# Maple6r.net
KiCad netlist of a schematic drawn in EAGLE
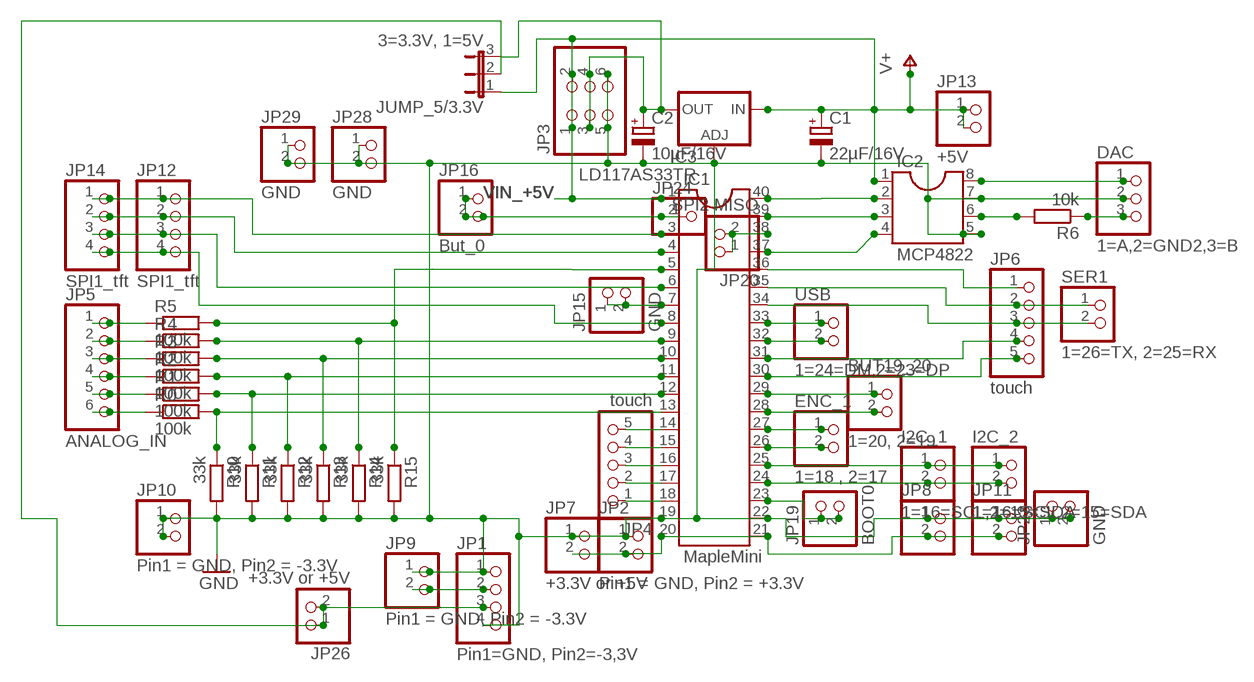
[diagram p0: schematic, sheet 1]

(export (version "E")
  (design (tool "Eeschema 10.0.6"))
  (components
    (comp (ref "BUT19_20")
      (value "1=20, 2=19")
      (footprint "eagle-import:1X02")
      (libsource (lib "eagle-import") (part "PINHD-1X2"))
    )
    (comp (ref "C1")
      (value "22µF/16V")
      (footprint "eagle-import:E5-8,5")
      (libsource (lib "eagle-import") (part "CPOL-EUE5-8.5"))
    )
    (comp (ref "C2")
      (value "10µF/16V")
      (footprint "eagle-import:E5-8,5")
      (libsource (lib "eagle-import") (part "CPOL-EUE5-8.5"))
    )
    (comp (ref "DAC")
      (value "1=A,2=GND2,3=B")
      (footprint "eagle-import:1X03")
      (libsource (lib "eagle-import") (part "PINHD-1X3"))
    )
    (comp (ref "ENC_1")
      (value "1=18 , 2=17")
      (footprint "eagle-import:1X02")
      (libsource (lib "eagle-import") (part "PINHD-1X2"))
    )
    (comp (ref "I2C_1")
      (value "1=16=SCL,2=15=SDA")
      (footprint "eagle-import:1X02")
      (libsource (lib "eagle-import") (part "PINHD-1X2"))
    )
    (comp (ref "I2C_2")
      (value "1=16=SCL,2=15=SDA")
      (footprint "eagle-import:1X02")
      (libsource (lib "eagle-import") (part "PINHD-1X2"))
    )
    (comp (ref "IC1")
      (value "MapleMini")
      (footprint "eagle-import:DIL40")
      (libsource (lib "eagle-import") (part "DIL40"))
    )
    (comp (ref "IC2")
      (value "MCP4822")
      (footprint "eagle-import:SOCKET-08")
      (libsource (lib "eagle-import") (part "DIL8S"))
    )
    (comp (ref "IC3")
      (value "LD117AS33TR")
      (footprint "eagle-import:SOT223")
      (libsource (lib "eagle-import") (part "LD117A?S33TR"))
    )
    (comp (ref "JP1")
      (value "Pin1=GND, Pin2=-3,3V")
      (footprint "eagle-import:1X04")
      (libsource (lib "eagle-import") (part "PINHD-1X4"))
    )
    (comp (ref "JP2")
      (value "Pin1 = GND, Pin2 = +3.3V")
      (footprint "eagle-import:1X02")
      (libsource (lib "eagle-import") (part "PINHD-1X2"))
    )
    (comp (ref "JP3")
      (value "PINHD-2X3")
      (footprint "eagle-import:2X03")
      (libsource (lib "eagle-import") (part "PINHD-2X3"))
    )
    (comp (ref "JP4")
      (value "touch")
      (footprint "eagle-import:1X05")
      (libsource (lib "eagle-import") (part "PINHD-1X5"))
    )
    (comp (ref "JP5")
      (value "ANALOG_IN")
      (footprint "eagle-import:1X06")
      (libsource (lib "eagle-import") (part "PINHD-1X6"))
    )
    (comp (ref "JP6")
      (value "touch")
      (footprint "eagle-import:1X05")
      (libsource (lib "eagle-import") (part "PINHD-1X5"))
    )
    (comp (ref "JP7")
      (value "+3.3V or +5V")
      (footprint "eagle-import:1X02")
      (libsource (lib "eagle-import") (part "PINHD-1X2"))
    )
    (comp (ref "JP8")
      (value "PINHD-1X2")
      (footprint "eagle-import:1X02")
      (libsource (lib "eagle-import") (part "PINHD-1X2"))
    )
    (comp (ref "JP9")
      (value "Pin1 = GND, Pin2 = -3.3V")
      (footprint "eagle-import:1X02")
      (libsource (lib "eagle-import") (part "PINHD-1X2"))
    )
    (comp (ref "JP10")
      (value "Pin1 = GND, Pin2 = -3.3V")
      (footprint "eagle-import:1X02")
      (libsource (lib "eagle-import") (part "PINHD-1X2"))
    )
    (comp (ref "JP11")
      (value "PINHD-1X2")
      (footprint "eagle-import:1X02")
      (libsource (lib "eagle-import") (part "PINHD-1X2"))
    )
    (comp (ref "JP12")
      (value "SPI1_tft")
      (footprint "eagle-import:1X04")
      (libsource (lib "eagle-import") (part "PINHD-1X4"))
    )
    (comp (ref "JP13")
      (value "+5V")
      (footprint "eagle-import:1X02")
      (libsource (lib "eagle-import") (part "PINHD-1X2"))
    )
    (comp (ref "JP14")
      (value "SPI1_tft")
      (footprint "eagle-import:1X04")
      (libsource (lib "eagle-import") (part "PINHD-1X4"))
    )
    (comp (ref "JP15")
      (value "GND")
      (footprint "eagle-import:1X02")
      (libsource (lib "eagle-import") (part "PINHD-1X2"))
    )
    (comp (ref "JP16")
      (value "But_0")
      (footprint "eagle-import:1X02")
      (libsource (lib "eagle-import") (part "PINHD-1X2"))
    )
    (comp (ref "JP19")
      (value "BOOT0")
      (footprint "eagle-import:1X02")
      (libsource (lib "eagle-import") (part "PINHD-1X2"))
    )
    (comp (ref "JP20")
      (value "SPI2 MISO")
      (footprint "eagle-import:1X02")
      (libsource (lib "eagle-import") (part "PINHD-1X2"))
    )
    (comp (ref "JP23")
      (value "GND")
      (footprint "eagle-import:1X02")
      (libsource (lib "eagle-import") (part "PINHD-1X2"))
    )
    (comp (ref "JP24")
      (value "PINHD-1X1")
      (footprint "eagle-import:1X01")
      (libsource (lib "eagle-import") (part "PINHD-1X1"))
    )
    (comp (ref "JP26")
      (value "+3.3V or +5V")
      (footprint "eagle-import:1X02")
      (libsource (lib "eagle-import") (part "PINHD-1X2"))
    )
    (comp (ref "JP28")
      (value "GND")
      (footprint "eagle-import:1X02")
      (libsource (lib "eagle-import") (part "PINHD-1X2"))
    )
    (comp (ref "JP29")
      (value "GND")
      (footprint "eagle-import:1X02")
      (libsource (lib "eagle-import") (part "PINHD-1X2"))
    )
    (comp (ref "JUMP_5/3.3V")
      (value "3=3.3V, 1=5V")
      (footprint "eagle-import:JP2")
      (libsource (lib "eagle-import") (part "JP2E"))
    )
    (comp (ref "R0")
      (value "100k")
      (footprint "eagle-import:0207_7")
      (libsource (lib "eagle-import") (part "R-EU_0207/7"))
    )
    (comp (ref "R1")
      (value "100k")
      (footprint "eagle-import:0207_7")
      (libsource (lib "eagle-import") (part "R-EU_0207/7"))
    )
    (comp (ref "R2")
      (value "100k")
      (footprint "eagle-import:0207_7")
      (libsource (lib "eagle-import") (part "R-EU_0207/7"))
    )
    (comp (ref "R3")
      (value "100k")
      (footprint "eagle-import:0207_7")
      (libsource (lib "eagle-import") (part "R-EU_0207/7"))
    )
    (comp (ref "R4")
      (value "100k")
      (footprint "eagle-import:0207_7")
      (libsource (lib "eagle-import") (part "R-EU_0207/7"))
    )
    (comp (ref "R5")
      (value "100k")
      (footprint "eagle-import:0207_7")
      (libsource (lib "eagle-import") (part "R-EU_0207/7"))
    )
    (comp (ref "R6")
      (value "10k")
      (footprint "eagle-import:0207_7")
      (libsource (lib "eagle-import") (part "R-EU_0207/7"))
    )
    (comp (ref "R10")
      (value "33k")
      (footprint "eagle-import:0207_7")
      (libsource (lib "eagle-import") (part "R-EU_0207/7"))
    )
    (comp (ref "R11")
      (value "33k")
      (footprint "eagle-import:0207_7")
      (libsource (lib "eagle-import") (part "R-EU_0207/7"))
    )
    (comp (ref "R12")
      (value "33k")
      (footprint "eagle-import:0207_7")
      (libsource (lib "eagle-import") (part "R-EU_0207/7"))
    )
    (comp (ref "R13")
      (value "33k")
      (footprint "eagle-import:0207_7")
      (libsource (lib "eagle-import") (part "R-EU_0207/7"))
    )
    (comp (ref "R14")
      (value "33k")
      (footprint "eagle-import:0207_7")
      (libsource (lib "eagle-import") (part "R-EU_0207/7"))
    )
    (comp (ref "R15")
      (value "33k")
      (footprint "eagle-import:0207_7")
      (libsource (lib "eagle-import") (part "R-EU_0207/7"))
    )
    (comp (ref "SER1")
      (value "1=26=TX, 2=25=RX")
      (footprint "eagle-import:1X02")
      (libsource (lib "eagle-import") (part "PINHD-1X2"))
    )
    (comp (ref "USB")
      (value "1=24=DM,2=23=DP")
      (footprint "eagle-import:1X02")
      (libsource (lib "eagle-import") (part "PINHD-1X2"))
    )
  )
  (nets
    (net (code "1") (name "GND") (class "Default")
      (node (ref "C1") (pin "-") (pinfunction "-_-") (pintype "passive"))
      (node (ref "C2") (pin "-") (pinfunction "-_-") (pintype "passive"))
      (node (ref "DAC") (pin "2") (pinfunction "2_2") (pintype "passive"))
      (node (ref "IC1") (pin "19") (pinfunction "19_19") (pintype "passive"))
      (node (ref "IC1") (pin "22") (pinfunction "22_22") (pintype "passive"))
      (node (ref "IC2") (pin "5") (pinfunction "5_5") (pintype "passive"))
      (node (ref "IC2") (pin "7") (pinfunction "7_7") (pintype "passive"))
      (node (ref "IC3") (pin "1") (pinfunction "ADJ_1") (pintype "input"))
      (node (ref "JP1") (pin "1") (pinfunction "1_1") (pintype "passive"))
      (node (ref "JP1") (pin "4") (pinfunction "4_4") (pintype "passive"))
      (node (ref "JP10") (pin "1") (pinfunction "1_1") (pintype "passive"))
      (node (ref "JP10") (pin "2") (pinfunction "2_2") (pintype "passive"))
      (node (ref "JP11") (pin "1") (pinfunction "1_1") (pintype "passive"))
      (node (ref "JP2") (pin "1") (pinfunction "1_1") (pintype "passive"))
      (node (ref "JP23") (pin "1") (pinfunction "1_1") (pintype "passive"))
      (node (ref "JP23") (pin "2") (pinfunction "2_2") (pintype "passive"))
      (node (ref "JP28") (pin "1") (pinfunction "1_1") (pintype "passive"))
      (node (ref "JP28") (pin "2") (pinfunction "2_2") (pintype "passive"))
      (node (ref "JP29") (pin "1") (pinfunction "1_1") (pintype "passive"))
      (node (ref "JP29") (pin "2") (pinfunction "2_2") (pintype "passive"))
      (node (ref "JP3") (pin "5") (pinfunction "5_5") (pintype "passive"))
      (node (ref "JP3") (pin "6") (pinfunction "6_6") (pintype "passive"))
      (node (ref "JP7") (pin "1") (pinfunction "1_1") (pintype "passive"))
      (node (ref "JP8") (pin "1") (pinfunction "1_1") (pintype "passive"))
      (node (ref "JP9") (pin "1") (pinfunction "1_1") (pintype "passive"))
      (node (ref "R10") (pin "2") (pinfunction "2_2") (pintype "passive"))
      (node (ref "R11") (pin "2") (pinfunction "2_2") (pintype "passive"))
      (node (ref "R12") (pin "2") (pinfunction "2_2") (pintype "passive"))
      (node (ref "R13") (pin "2") (pinfunction "2_2") (pintype "passive"))
      (node (ref "R14") (pin "2") (pinfunction "2_2") (pintype "passive"))
      (node (ref "R15") (pin "2") (pinfunction "2_2") (pintype "passive"))
    )
    (net (code "2") (name "Net-(BUT19_20-Pad1)") (class "Default")
      (node (ref "BUT19_20") (pin "1") (pinfunction "1_1") (pintype "passive"))
      (node (ref "IC1") (pin "29") (pinfunction "29_29") (pintype "passive"))
    )
    (net (code "3") (name "Net-(BUT19_20-Pad2)") (class "Default")
      (node (ref "BUT19_20") (pin "2") (pinfunction "2_2") (pintype "passive"))
      (node (ref "IC1") (pin "28") (pinfunction "28_28") (pintype "passive"))
    )
    (net (code "4") (name "Net-(DAC-Pad1)") (class "Default")
      (node (ref "DAC") (pin "1") (pinfunction "1_1") (pintype "passive"))
      (node (ref "IC2") (pin "8") (pinfunction "8_8") (pintype "passive"))
    )
    (net (code "5") (name "Net-(DAC-Pad3)") (class "Default")
      (node (ref "DAC") (pin "3") (pinfunction "3_3") (pintype "passive"))
      (node (ref "R6") (pin "1") (pinfunction "1_1") (pintype "passive"))
    )
    (net (code "6") (name "Net-(ENC_1-Pad1)") (class "Default")
      (node (ref "ENC_1") (pin "1") (pinfunction "1_1") (pintype "passive"))
      (node (ref "IC1") (pin "27") (pinfunction "27_27") (pintype "passive"))
    )
    (net (code "7") (name "Net-(ENC_1-Pad2)") (class "Default")
      (node (ref "ENC_1") (pin "2") (pinfunction "2_2") (pintype "passive"))
      (node (ref "IC1") (pin "26") (pinfunction "26_26") (pintype "passive"))
    )
    (net (code "8") (name "Net-(I2C_1-Pad1)") (class "Default")
      (node (ref "I2C_1") (pin "1") (pinfunction "1_1") (pintype "passive"))
      (node (ref "I2C_2") (pin "1") (pinfunction "1_1") (pintype "passive"))
      (node (ref "IC1") (pin "25") (pinfunction "25_25") (pintype "passive"))
    )
    (net (code "9") (name "Net-(I2C_1-Pad2)") (class "Default")
      (node (ref "I2C_1") (pin "2") (pinfunction "2_2") (pintype "passive"))
      (node (ref "I2C_2") (pin "2") (pinfunction "2_2") (pintype "passive"))
      (node (ref "IC1") (pin "24") (pinfunction "24_24") (pintype "passive"))
    )
    (net (code "10") (name "Net-(IC1-Pad2)") (class "Default")
      (node (ref "IC1") (pin "2") (pinfunction "2_2") (pintype "passive"))
      (node (ref "JP16") (pin "1") (pinfunction "1_1") (pintype "passive"))
      (node (ref "JP16") (pin "2") (pinfunction "2_2") (pintype "passive"))
      (node (ref "JP24") (pin "1") (pinfunction "1_1") (pintype "passive"))
    )
    (net (code "11") (name "Net-(IC1-Pad3)") (class "Default")
      (node (ref "IC1") (pin "3") (pinfunction "3_3") (pintype "passive"))
      (node (ref "JP12") (pin "1") (pinfunction "1_1") (pintype "passive"))
      (node (ref "JP14") (pin "1") (pinfunction "1_1") (pintype "passive"))
    )
    (net (code "12") (name "Net-(IC1-Pad4)") (class "Default")
      (node (ref "IC1") (pin "4") (pinfunction "4_4") (pintype "passive"))
      (node (ref "JP12") (pin "2") (pinfunction "2_2") (pintype "passive"))
      (node (ref "JP14") (pin "2") (pinfunction "2_2") (pintype "passive"))
    )
    (net (code "13") (name "Net-(IC1-Pad5)") (class "Default")
      (node (ref "IC1") (pin "5") (pinfunction "5_5") (pintype "passive"))
      (node (ref "R15") (pin "1") (pinfunction "1_1") (pintype "passive"))
      (node (ref "R5") (pin "2") (pinfunction "2_2") (pintype "passive"))
    )
    (net (code "14") (name "Net-(IC1-Pad6)") (class "Default")
      (node (ref "IC1") (pin "6") (pinfunction "6_6") (pintype "passive"))
      (node (ref "JP12") (pin "3") (pinfunction "3_3") (pintype "passive"))
      (node (ref "JP14") (pin "3") (pinfunction "3_3") (pintype "passive"))
    )
    (net (code "15") (name "Net-(IC1-Pad7)") (class "Default")
      (node (ref "IC1") (pin "7") (pinfunction "7_7") (pintype "passive"))
      (node (ref "JP15") (pin "1") (pinfunction "1_1") (pintype "passive"))
      (node (ref "JP15") (pin "2") (pinfunction "2_2") (pintype "passive"))
    )
    (net (code "16") (name "Net-(IC1-Pad8)") (class "Default")
      (node (ref "IC1") (pin "8") (pinfunction "8_8") (pintype "passive"))
      (node (ref "JP12") (pin "4") (pinfunction "4_4") (pintype "passive"))
      (node (ref "JP14") (pin "4") (pinfunction "4_4") (pintype "passive"))
    )
    (net (code "17") (name "Net-(IC1-Pad9)") (class "Default")
      (node (ref "IC1") (pin "9") (pinfunction "9_9") (pintype "passive"))
      (node (ref "R14") (pin "1") (pinfunction "1_1") (pintype "passive"))
      (node (ref "R4") (pin "2") (pinfunction "2_2") (pintype "passive"))
    )
    (net (code "18") (name "Net-(IC1-Pad10)") (class "Default")
      (node (ref "IC1") (pin "10") (pinfunction "10_10") (pintype "passive"))
      (node (ref "R13") (pin "1") (pinfunction "1_1") (pintype "passive"))
      (node (ref "R3") (pin "2") (pinfunction "2_2") (pintype "passive"))
    )
    (net (code "19") (name "Net-(IC1-Pad11)") (class "Default")
      (node (ref "IC1") (pin "11") (pinfunction "11_11") (pintype "passive"))
      (node (ref "R12") (pin "1") (pinfunction "1_1") (pintype "passive"))
      (node (ref "R2") (pin "2") (pinfunction "2_2") (pintype "passive"))
    )
    (net (code "20") (name "Net-(IC1-Pad12)") (class "Default")
      (node (ref "IC1") (pin "12") (pinfunction "12_12") (pintype "passive"))
      (node (ref "R1") (pin "2") (pinfunction "2_2") (pintype "passive"))
      (node (ref "R11") (pin "1") (pinfunction "1_1") (pintype "passive"))
    )
    (net (code "21") (name "Net-(IC1-Pad13)") (class "Default")
      (node (ref "IC1") (pin "13") (pinfunction "13_13") (pintype "passive"))
      (node (ref "R0") (pin "2") (pinfunction "2_2") (pintype "passive"))
      (node (ref "R10") (pin "1") (pinfunction "1_1") (pintype "passive"))
    )
    (net (code "22") (name "Net-(IC1-Pad14)") (class "Default")
      (node (ref "IC1") (pin "14") (pinfunction "14_14") (pintype "passive"))
      (node (ref "JP4") (pin "5") (pinfunction "5_5") (pintype "passive"))
    )
    (net (code "23") (name "Net-(IC1-Pad15)") (class "Default")
      (node (ref "IC1") (pin "15") (pinfunction "15_15") (pintype "passive"))
      (node (ref "JP4") (pin "4") (pinfunction "4_4") (pintype "passive"))
    )
    (net (code "24") (name "Net-(IC1-Pad16)") (class "Default")
      (node (ref "IC1") (pin "16") (pinfunction "16_16") (pintype "passive"))
      (node (ref "JP4") (pin "3") (pinfunction "3_3") (pintype "passive"))
    )
    (net (code "25") (name "Net-(IC1-Pad17)") (class "Default")
      (node (ref "IC1") (pin "17") (pinfunction "17_17") (pintype "passive"))
      (node (ref "JP4") (pin "2") (pinfunction "2_2") (pintype "passive"))
    )
    (net (code "26") (name "Net-(IC1-Pad18)") (class "Default")
      (node (ref "IC1") (pin "18") (pinfunction "18_18") (pintype "passive"))
      (node (ref "JP4") (pin "1") (pinfunction "1_1") (pintype "passive"))
    )
    (net (code "27") (name "Net-(IC1-Pad20)") (class "Default")
      (node (ref "IC1") (pin "20") (pinfunction "20_20") (pintype "passive"))
      (node (ref "IC1") (pin "21") (pinfunction "21_21") (pintype "passive"))
      (node (ref "JP11") (pin "2") (pinfunction "2_2") (pintype "passive"))
      (node (ref "JP2") (pin "2") (pinfunction "2_2") (pintype "passive"))
      (node (ref "JP7") (pin "2") (pinfunction "2_2") (pintype "passive"))
      (node (ref "JP8") (pin "2") (pinfunction "2_2") (pintype "passive"))
    )
    (net (code "28") (name "Net-(IC1-Pad23)") (class "Default")
      (node (ref "IC1") (pin "23") (pinfunction "23_23") (pintype "passive"))
      (node (ref "JP19") (pin "1") (pinfunction "1_1") (pintype "passive"))
      (node (ref "JP19") (pin "2") (pinfunction "2_2") (pintype "passive"))
    )
    (net (code "29") (name "Net-(IC1-Pad30)") (class "Default")
      (node (ref "IC1") (pin "30") (pinfunction "30_30") (pintype "passive"))
      (node (ref "JP6") (pin "5") (pinfunction "5_5") (pintype "passive"))
    )
    (net (code "30") (name "Net-(IC1-Pad31)") (class "Default")
      (node (ref "IC1") (pin "31") (pinfunction "31_31") (pintype "passive"))
      (node (ref "JP6") (pin "4") (pinfunction "4_4") (pintype "passive"))
    )
    (net (code "31") (name "Net-(IC1-Pad32)") (class "Default")
      (node (ref "IC1") (pin "32") (pinfunction "32_32") (pintype "passive"))
      (node (ref "USB") (pin "2") (pinfunction "2_2") (pintype "passive"))
    )
    (net (code "32") (name "Net-(IC1-Pad33)") (class "Default")
      (node (ref "IC1") (pin "33") (pinfunction "33_33") (pintype "passive"))
      (node (ref "USB") (pin "1") (pinfunction "1_1") (pintype "passive"))
    )
    (net (code "33") (name "Net-(IC1-Pad34)") (class "Default")
      (node (ref "IC1") (pin "34") (pinfunction "34_34") (pintype "passive"))
      (node (ref "JP6") (pin "3") (pinfunction "3_3") (pintype "passive"))
      (node (ref "SER1") (pin "2") (pinfunction "2_2") (pintype "passive"))
    )
    (net (code "34") (name "Net-(IC1-Pad35)") (class "Default")
      (node (ref "IC1") (pin "35") (pinfunction "35_35") (pintype "passive"))
      (node (ref "JP6") (pin "2") (pinfunction "2_2") (pintype "passive"))
      (node (ref "SER1") (pin "1") (pinfunction "1_1") (pintype "passive"))
    )
    (net (code "35") (name "Net-(IC1-Pad36)") (class "Default")
      (node (ref "IC1") (pin "36") (pinfunction "36_36") (pintype "passive"))
      (node (ref "JP6") (pin "1") (pinfunction "1_1") (pintype "passive"))
    )
    (net (code "36") (name "Net-(IC1-Pad37)") (class "Default")
      (node (ref "IC1") (pin "37") (pinfunction "37_37") (pintype "passive"))
      (node (ref "IC2") (pin "4") (pinfunction "4_4") (pintype "passive"))
    )
    (net (code "37") (name "Net-(IC1-Pad38)") (class "Default")
      (node (ref "IC1") (pin "38") (pinfunction "38_38") (pintype "passive"))
      (node (ref "JP20") (pin "1") (pinfunction "1_1") (pintype "passive"))
      (node (ref "JP20") (pin "2") (pinfunction "2_2") (pintype "passive"))
    )
    (net (code "38") (name "Net-(IC1-Pad39)") (class "Default")
      (node (ref "IC1") (pin "39") (pinfunction "39_39") (pintype "passive"))
      (node (ref "IC2") (pin "3") (pinfunction "3_3") (pintype "passive"))
    )
    (net (code "39") (name "Net-(IC1-Pad40)") (class "Default")
      (node (ref "IC1") (pin "40") (pinfunction "40_40") (pintype "passive"))
      (node (ref "IC2") (pin "2") (pinfunction "2_2") (pintype "passive"))
    )
    (net (code "40") (name "Net-(IC2-Pad6)") (class "Default")
      (node (ref "IC2") (pin "6") (pinfunction "6_6") (pintype "passive"))
      (node (ref "R6") (pin "2") (pinfunction "2_2") (pintype "passive"))
    )
    (net (code "41") (name "Net-(IC3-OUT)") (class "Default")
      (node (ref "C2") (pin "+") (pinfunction "+_+") (pintype "passive"))
      (node (ref "IC3") (pin "4") (pinfunction "OUT_4") (pintype "passive"))
      (node (ref "JP3") (pin "3") (pinfunction "3_3") (pintype "passive"))
      (node (ref "JP3") (pin "4") (pinfunction "4_4") (pintype "passive"))
      (node (ref "JUMP_5/3.3V") (pin "3") (pinfunction "3_3") (pintype "passive"))
    )
    (net (code "42") (name "Net-(JP1-Pad2)") (class "Default")
      (node (ref "JP1") (pin "2") (pinfunction "2_2") (pintype "passive"))
      (node (ref "JP9") (pin "2") (pinfunction "2_2") (pintype "passive"))
    )
    (net (code "43") (name "Net-(JP1-Pad3)") (class "Default")
      (node (ref "JP1") (pin "3") (pinfunction "3_3") (pintype "passive"))
      (node (ref "JP26") (pin "1") (pinfunction "1_1") (pintype "passive"))
      (node (ref "JP26") (pin "2") (pinfunction "2_2") (pintype "passive"))
      (node (ref "JUMP_5/3.3V") (pin "2") (pinfunction "2_2") (pintype "passive"))
    )
    (net (code "44") (name "Net-(JP5-Pad1)") (class "Default")
      (node (ref "JP5") (pin "1") (pinfunction "1_1") (pintype "passive"))
      (node (ref "R5") (pin "1") (pinfunction "1_1") (pintype "passive"))
    )
    (net (code "45") (name "Net-(JP5-Pad2)") (class "Default")
      (node (ref "JP5") (pin "2") (pinfunction "2_2") (pintype "passive"))
      (node (ref "R4") (pin "1") (pinfunction "1_1") (pintype "passive"))
    )
    (net (code "46") (name "Net-(JP5-Pad3)") (class "Default")
      (node (ref "JP5") (pin "3") (pinfunction "3_3") (pintype "passive"))
      (node (ref "R3") (pin "1") (pinfunction "1_1") (pintype "passive"))
    )
    (net (code "47") (name "Net-(JP5-Pad4)") (class "Default")
      (node (ref "JP5") (pin "4") (pinfunction "4_4") (pintype "passive"))
      (node (ref "R2") (pin "1") (pinfunction "1_1") (pintype "passive"))
    )
    (net (code "48") (name "Net-(JP5-Pad5)") (class "Default")
      (node (ref "JP5") (pin "5") (pinfunction "5_5") (pintype "passive"))
      (node (ref "R1") (pin "1") (pinfunction "1_1") (pintype "passive"))
    )
    (net (code "49") (name "Net-(JP5-Pad6)") (class "Default")
      (node (ref "JP5") (pin "6") (pinfunction "6_6") (pintype "passive"))
      (node (ref "R0") (pin "1") (pinfunction "1_1") (pintype "passive"))
    )
    (net (code "50") (name "V+") (class "Default")
      (node (ref "C1") (pin "+") (pinfunction "+_+") (pintype "passive"))
      (node (ref "IC1") (pin "1") (pinfunction "1_1") (pintype "passive"))
      (node (ref "IC2") (pin "1") (pinfunction "1_1") (pintype "passive"))
      (node (ref "IC3") (pin "3") (pinfunction "IN_3") (pintype "input"))
      (node (ref "JP13") (pin "1") (pinfunction "1_1") (pintype "passive"))
      (node (ref "JP13") (pin "2") (pinfunction "2_2") (pintype "passive"))
      (node (ref "JP3") (pin "1") (pinfunction "1_1") (pintype "passive"))
      (node (ref "JP3") (pin "2") (pinfunction "2_2") (pintype "passive"))
      (node (ref "JUMP_5/3.3V") (pin "1") (pinfunction "1_1") (pintype "passive"))
    )
  )
)
